# moter.net
KiCad netlist of a schematic drawn in EAGLE
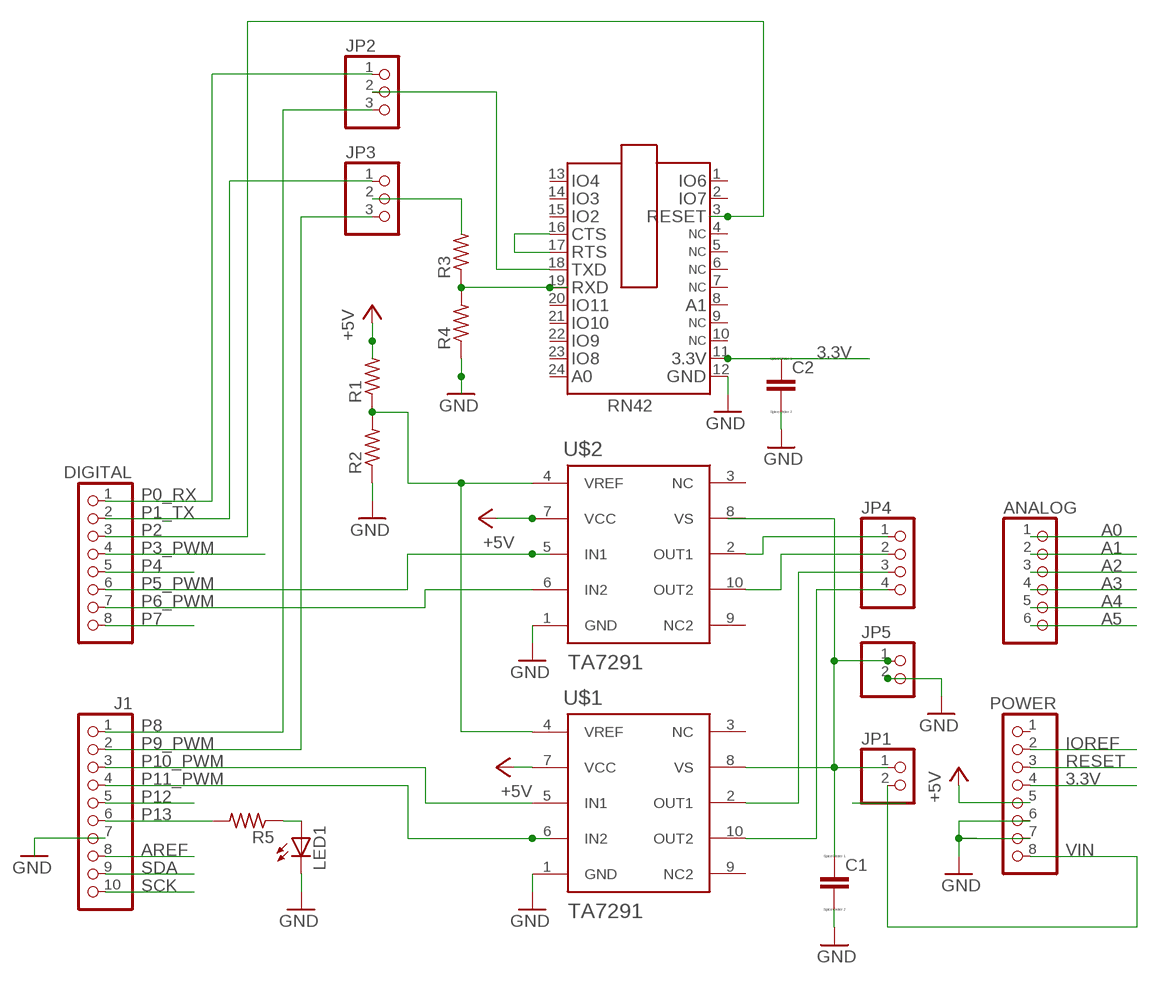
[diagram p0: schematic, sheet 1]

(export (version "E")
  (design (tool "Eeschema 10.0.6"))
  (components
    (comp (ref "ANALOG")
      (value "PINHD-1X6")
      (footprint "eagle-import:1X06")
      (libsource (lib "eagle-import") (part "PINHD-1X6"))
    )
    (comp (ref "C1")
      (value "C-EU050-025X075")
      (footprint "eagle-import:C050-025X075")
      (libsource (lib "eagle-import") (part "C-EU050-025X075"))
    )
    (comp (ref "C2")
      (value "C-EU050-025X075")
      (footprint "eagle-import:C050-025X075")
      (libsource (lib "eagle-import") (part "C-EU050-025X075"))
    )
    (comp (ref "DIGITAL")
      (value "PINHD-1X8TH")
      (footprint "eagle-import:1X08-TH")
      (libsource (lib "eagle-import") (part "PINHD-1X8TH"))
    )
    (comp (ref "IC1")
      (value "RN42-9")
      (footprint "eagle-import:RN42-PKG")
      (libsource (lib "eagle-import") (part "RN42-9"))
    )
    (comp (ref "J1")
      (value "PINHD-1X10TH")
      (footprint "eagle-import:1X10-TH")
      (libsource (lib "eagle-import") (part "PINHD-1X10TH"))
    )
    (comp (ref "JP1")
      (value "PINHD-1X2")
      (footprint "eagle-import:1X02")
      (libsource (lib "eagle-import") (part "PINHD-1X2"))
    )
    (comp (ref "JP2")
      (value "PINHD-1X3")
      (footprint "eagle-import:1X03")
      (libsource (lib "eagle-import") (part "PINHD-1X3"))
    )
    (comp (ref "JP3")
      (value "PINHD-1X3")
      (footprint "eagle-import:1X03")
      (libsource (lib "eagle-import") (part "PINHD-1X3"))
    )
    (comp (ref "JP4")
      (value "PINHD-1X4")
      (footprint "eagle-import:1X04")
      (libsource (lib "eagle-import") (part "PINHD-1X4"))
    )
    (comp (ref "JP5")
      (value "PINHD-1X2")
      (footprint "eagle-import:1X02")
      (libsource (lib "eagle-import") (part "PINHD-1X2"))
    )
    (comp (ref "LED1")
      (value "LED3MM")
      (footprint "eagle-import:LED3MM")
      (libsource (lib "eagle-import") (part "LED3MM"))
    )
    (comp (ref "POWER")
      (value "PINHD-1X8TH")
      (footprint "eagle-import:1X08-TH")
      (libsource (lib "eagle-import") (part "PINHD-1X8TH"))
    )
    (comp (ref "R1")
      (value "R-US_0207/10")
      (footprint "eagle-import:0207_10")
      (libsource (lib "eagle-import") (part "R-US_0207/10"))
    )
    (comp (ref "R2")
      (value "R-US_0207/10")
      (footprint "eagle-import:0207_10")
      (libsource (lib "eagle-import") (part "R-US_0207/10"))
    )
    (comp (ref "R3")
      (value "R-US_0207/10")
      (footprint "eagle-import:0207_10")
      (libsource (lib "eagle-import") (part "R-US_0207/10"))
    )
    (comp (ref "R4")
      (value "R-US_0207/10")
      (footprint "eagle-import:0207_10")
      (libsource (lib "eagle-import") (part "R-US_0207/10"))
    )
    (comp (ref "R5")
      (value "R-US_0207/10")
      (footprint "eagle-import:0207_10")
      (libsource (lib "eagle-import") (part "R-US_0207/10"))
    )
    (comp (ref "U$1")
      (value "TA7291")
      (footprint "eagle-import:HSIP10")
      (libsource (lib "eagle-import") (part "TA7291"))
    )
    (comp (ref "U$2")
      (value "TA7291")
      (footprint "eagle-import:HSIP10")
      (libsource (lib "eagle-import") (part "TA7291"))
    )
  )
  (nets
    (net (code "1") (name "+5V") (class "Default")
      (node (ref "POWER") (pin "5") (pinfunction "5_5") (pintype "passive"))
      (node (ref "R1") (pin "2") (pinfunction "2_2") (pintype "passive"))
      (node (ref "U$1") (pin "7") (pinfunction "VCC_7") (pintype "bidirectional"))
      (node (ref "U$2") (pin "7") (pinfunction "VCC_7") (pintype "bidirectional"))
    )
    (net (code "2") (name "/3.3V") (class "Default")
      (node (ref "C2") (pin "1") (pinfunction "1_1") (pintype "passive"))
      (node (ref "IC1") (pin "11") (pinfunction "11_11") (pintype "passive"))
      (node (ref "POWER") (pin "4") (pinfunction "4_4") (pintype "passive"))
    )
    (net (code "3") (name "/A0") (class "Default")
      (node (ref "ANALOG") (pin "1") (pinfunction "1_1") (pintype "passive"))
    )
    (net (code "4") (name "/A1") (class "Default")
      (node (ref "ANALOG") (pin "2") (pinfunction "2_2") (pintype "passive"))
    )
    (net (code "5") (name "/A2") (class "Default")
      (node (ref "ANALOG") (pin "3") (pinfunction "3_3") (pintype "passive"))
    )
    (net (code "6") (name "/A3") (class "Default")
      (node (ref "ANALOG") (pin "4") (pinfunction "4_4") (pintype "passive"))
    )
    (net (code "7") (name "/A4") (class "Default")
      (node (ref "ANALOG") (pin "5") (pinfunction "5_5") (pintype "passive"))
    )
    (net (code "8") (name "/A5") (class "Default")
      (node (ref "ANALOG") (pin "6") (pinfunction "6_6") (pintype "passive"))
    )
    (net (code "9") (name "/AREF") (class "Default")
      (node (ref "J1") (pin "8") (pinfunction "8_8") (pintype "passive"))
    )
    (net (code "10") (name "/IOREF") (class "Default")
      (node (ref "POWER") (pin "2") (pinfunction "2_2") (pintype "passive"))
    )
    (net (code "11") (name "/P0_RX") (class "Default")
      (node (ref "DIGITAL") (pin "1") (pinfunction "1_1") (pintype "passive"))
      (node (ref "JP2") (pin "1") (pinfunction "1_1") (pintype "passive"))
    )
    (net (code "12") (name "/P1_TX") (class "Default")
      (node (ref "DIGITAL") (pin "2") (pinfunction "2_2") (pintype "passive"))
      (node (ref "JP3") (pin "1") (pinfunction "1_1") (pintype "passive"))
    )
    (net (code "13") (name "/P2") (class "Default")
      (node (ref "DIGITAL") (pin "3") (pinfunction "3_3") (pintype "passive"))
      (node (ref "IC1") (pin "3") (pinfunction "3_3") (pintype "passive"))
    )
    (net (code "14") (name "/P3_PWM") (class "Default")
      (node (ref "DIGITAL") (pin "4") (pinfunction "4_4") (pintype "passive"))
    )
    (net (code "15") (name "/P4") (class "Default")
      (node (ref "DIGITAL") (pin "5") (pinfunction "5_5") (pintype "passive"))
    )
    (net (code "16") (name "/P5_PWM") (class "Default")
      (node (ref "DIGITAL") (pin "6") (pinfunction "6_6") (pintype "passive"))
      (node (ref "U$2") (pin "5") (pinfunction "IN1_5") (pintype "bidirectional"))
    )
    (net (code "17") (name "/P6_PWM") (class "Default")
      (node (ref "DIGITAL") (pin "7") (pinfunction "7_7") (pintype "passive"))
      (node (ref "U$2") (pin "6") (pinfunction "IN2_6") (pintype "bidirectional"))
    )
    (net (code "18") (name "/P7") (class "Default")
      (node (ref "DIGITAL") (pin "8") (pinfunction "8_8") (pintype "passive"))
    )
    (net (code "19") (name "/P8") (class "Default")
      (node (ref "J1") (pin "1") (pinfunction "1_1") (pintype "passive"))
      (node (ref "JP2") (pin "3") (pinfunction "3_3") (pintype "passive"))
    )
    (net (code "20") (name "/P9_PWM") (class "Default")
      (node (ref "J1") (pin "2") (pinfunction "2_2") (pintype "passive"))
      (node (ref "JP3") (pin "3") (pinfunction "3_3") (pintype "passive"))
    )
    (net (code "21") (name "/P10_PWM") (class "Default")
      (node (ref "J1") (pin "3") (pinfunction "3_3") (pintype "passive"))
      (node (ref "U$1") (pin "5") (pinfunction "IN1_5") (pintype "bidirectional"))
    )
    (net (code "22") (name "/P11_PWM") (class "Default")
      (node (ref "J1") (pin "4") (pinfunction "4_4") (pintype "passive"))
      (node (ref "U$1") (pin "6") (pinfunction "IN2_6") (pintype "bidirectional"))
    )
    (net (code "23") (name "/P12") (class "Default")
      (node (ref "J1") (pin "5") (pinfunction "5_5") (pintype "passive"))
    )
    (net (code "24") (name "/P13") (class "Default")
      (node (ref "J1") (pin "6") (pinfunction "6_6") (pintype "passive"))
      (node (ref "R5") (pin "2") (pinfunction "2_2") (pintype "passive"))
    )
    (net (code "25") (name "/RESET") (class "Default")
      (node (ref "POWER") (pin "3") (pinfunction "3_3") (pintype "passive"))
    )
    (net (code "26") (name "/SCK") (class "Default")
      (node (ref "J1") (pin "10") (pinfunction "10_10") (pintype "passive"))
    )
    (net (code "27") (name "/SDA") (class "Default")
      (node (ref "J1") (pin "9") (pinfunction "9_9") (pintype "passive"))
    )
    (net (code "28") (name "/VIN") (class "Default")
      (node (ref "JP1") (pin "2") (pinfunction "2_2") (pintype "passive"))
      (node (ref "POWER") (pin "8") (pinfunction "8_8") (pintype "passive"))
    )
    (net (code "29") (name "/VS") (class "Default")
      (node (ref "C1") (pin "1") (pinfunction "1_1") (pintype "passive"))
      (node (ref "JP1") (pin "1") (pinfunction "1_1") (pintype "passive"))
      (node (ref "JP5") (pin "1") (pinfunction "1_1") (pintype "passive"))
      (node (ref "U$1") (pin "8") (pinfunction "VS_8") (pintype "bidirectional"))
      (node (ref "U$2") (pin "8") (pinfunction "VS_8") (pintype "bidirectional"))
    )
    (net (code "30") (name "GND") (class "Default")
      (node (ref "C1") (pin "2") (pinfunction "2_2") (pintype "passive"))
      (node (ref "C2") (pin "2") (pinfunction "2_2") (pintype "passive"))
      (node (ref "IC1") (pin "12") (pinfunction "12_12") (pintype "passive"))
      (node (ref "J1") (pin "7") (pinfunction "7_7") (pintype "passive"))
      (node (ref "JP5") (pin "2") (pinfunction "2_2") (pintype "passive"))
      (node (ref "LED1") (pin "K") (pinfunction "C_K") (pintype "passive"))
      (node (ref "POWER") (pin "6") (pinfunction "6_6") (pintype "passive"))
      (node (ref "POWER") (pin "7") (pinfunction "7_7") (pintype "passive"))
      (node (ref "R2") (pin "1") (pinfunction "1_1") (pintype "passive"))
      (node (ref "R4") (pin "1") (pinfunction "1_1") (pintype "passive"))
      (node (ref "U$1") (pin "1") (pinfunction "GND_1") (pintype "bidirectional"))
      (node (ref "U$2") (pin "1") (pinfunction "GND_1") (pintype "bidirectional"))
    )
    (net (code "31") (name "Net-(IC1-Pad16)") (class "Default")
      (node (ref "IC1") (pin "16") (pinfunction "16_16") (pintype "passive"))
      (node (ref "IC1") (pin "17") (pinfunction "17_17") (pintype "passive"))
    )
    (net (code "32") (name "Net-(IC1-Pad18)") (class "Default")
      (node (ref "IC1") (pin "18") (pinfunction "18_18") (pintype "passive"))
      (node (ref "JP2") (pin "2") (pinfunction "2_2") (pintype "passive"))
    )
    (net (code "33") (name "Net-(IC1-Pad19)") (class "Default")
      (node (ref "IC1") (pin "19") (pinfunction "19_19") (pintype "passive"))
      (node (ref "R3") (pin "1") (pinfunction "1_1") (pintype "passive"))
      (node (ref "R4") (pin "2") (pinfunction "2_2") (pintype "passive"))
    )
    (net (code "34") (name "Net-(JP3-Pad2)") (class "Default")
      (node (ref "JP3") (pin "2") (pinfunction "2_2") (pintype "passive"))
      (node (ref "R3") (pin "2") (pinfunction "2_2") (pintype "passive"))
    )
    (net (code "35") (name "Net-(LED1-PadA)") (class "Default")
      (node (ref "LED1") (pin "A") (pinfunction "A_A") (pintype "passive"))
      (node (ref "R5") (pin "1") (pinfunction "1_1") (pintype "passive"))
    )
    (net (code "36") (name "Net-(U$1-OUT1)") (class "Default")
      (node (ref "JP4") (pin "3") (pinfunction "3_3") (pintype "passive"))
      (node (ref "U$1") (pin "2") (pinfunction "OUT1_2") (pintype "bidirectional"))
    )
    (net (code "37") (name "Net-(U$1-OUT2)") (class "Default")
      (node (ref "JP4") (pin "4") (pinfunction "4_4") (pintype "passive"))
      (node (ref "U$1") (pin "10") (pinfunction "OUT2_10") (pintype "bidirectional"))
    )
    (net (code "38") (name "Net-(U$1-VREF)") (class "Default")
      (node (ref "R1") (pin "1") (pinfunction "1_1") (pintype "passive"))
      (node (ref "R2") (pin "2") (pinfunction "2_2") (pintype "passive"))
      (node (ref "U$1") (pin "4") (pinfunction "VREF_4") (pintype "bidirectional"))
      (node (ref "U$2") (pin "4") (pinfunction "VREF_4") (pintype "bidirectional"))
    )
    (net (code "39") (name "Net-(U$2-OUT1)") (class "Default")
      (node (ref "JP4") (pin "1") (pinfunction "1_1") (pintype "passive"))
      (node (ref "U$2") (pin "2") (pinfunction "OUT1_2") (pintype "bidirectional"))
    )
    (net (code "40") (name "Net-(U$2-OUT2)") (class "Default")
      (node (ref "JP4") (pin "2") (pinfunction "2_2") (pintype "passive"))
      (node (ref "U$2") (pin "10") (pinfunction "OUT2_10") (pintype "bidirectional"))
    )
    (net (code "41") (name "unconnected-(IC1-Pad1)") (class "Default")
      (node (ref "IC1") (pin "1") (pinfunction "1_1") (pintype "passive"))
    )
    (net (code "42") (name "unconnected-(IC1-Pad2)") (class "Default")
      (node (ref "IC1") (pin "2") (pinfunction "2_2") (pintype "passive"))
    )
    (net (code "43") (name "unconnected-(IC1-Pad4)") (class "Default")
      (node (ref "IC1") (pin "4") (pinfunction "4_4") (pintype "passive"))
    )
    (net (code "44") (name "unconnected-(IC1-Pad5)") (class "Default")
      (node (ref "IC1") (pin "5") (pinfunction "5_5") (pintype "passive"))
    )
    (net (code "45") (name "unconnected-(IC1-Pad6)") (class "Default")
      (node (ref "IC1") (pin "6") (pinfunction "6_6") (pintype "passive"))
    )
    (net (code "46") (name "unconnected-(IC1-Pad7)") (class "Default")
      (node (ref "IC1") (pin "7") (pinfunction "7_7") (pintype "passive"))
    )
    (net (code "47") (name "unconnected-(IC1-Pad8)") (class "Default")
      (node (ref "IC1") (pin "8") (pinfunction "8_8") (pintype "passive"))
    )
    (net (code "48") (name "unconnected-(IC1-Pad9)") (class "Default")
      (node (ref "IC1") (pin "9") (pinfunction "9_9") (pintype "passive"))
    )
    (net (code "49") (name "unconnected-(IC1-Pad10)") (class "Default")
      (node (ref "IC1") (pin "10") (pinfunction "10_10") (pintype "passive"))
    )
    (net (code "50") (name "unconnected-(IC1-Pad13)") (class "Default")
      (node (ref "IC1") (pin "13") (pinfunction "13_13") (pintype "passive"))
    )
    (net (code "51") (name "unconnected-(IC1-Pad14)") (class "Default")
      (node (ref "IC1") (pin "14") (pinfunction "14_14") (pintype "passive"))
    )
    (net (code "52") (name "unconnected-(IC1-Pad15)") (class "Default")
      (node (ref "IC1") (pin "15") (pinfunction "15_15") (pintype "passive"))
    )
    (net (code "53") (name "unconnected-(IC1-Pad20)") (class "Default")
      (node (ref "IC1") (pin "20") (pinfunction "20_20") (pintype "passive"))
    )
    (net (code "54") (name "unconnected-(IC1-Pad21)") (class "Default")
      (node (ref "IC1") (pin "21") (pinfunction "21_21") (pintype "passive"))
    )
    (net (code "55") (name "unconnected-(IC1-Pad22)") (class "Default")
      (node (ref "IC1") (pin "22") (pinfunction "22_22") (pintype "passive"))
    )
    (net (code "56") (name "unconnected-(IC1-Pad23)") (class "Default")
      (node (ref "IC1") (pin "23") (pinfunction "23_23") (pintype "passive"))
    )
    (net (code "57") (name "unconnected-(IC1-Pad24)") (class "Default")
      (node (ref "IC1") (pin "24") (pinfunction "24_24") (pintype "passive"))
    )
    (net (code "58") (name "unconnected-(POWER-Pad1)") (class "Default")
      (node (ref "POWER") (pin "1") (pinfunction "1_1") (pintype "passive"))
    )
    (net (code "59") (name "unconnected-(U$1-NC-Pad3)") (class "Default")
      (node (ref "U$1") (pin "3") (pinfunction "NC_3") (pintype "bidirectional"))
    )
    (net (code "60") (name "unconnected-(U$1-NC2-Pad9)") (class "Default")
      (node (ref "U$1") (pin "9") (pinfunction "NC2_9") (pintype "bidirectional"))
    )
    (net (code "61") (name "unconnected-(U$2-NC-Pad3)") (class "Default")
      (node (ref "U$2") (pin "3") (pinfunction "NC_3") (pintype "bidirectional"))
    )
    (net (code "62") (name "unconnected-(U$2-NC2-Pad9)") (class "Default")
      (node (ref "U$2") (pin "9") (pinfunction "NC2_9") (pintype "bidirectional"))
    )
  )
)
